# current_sense.net
KiCad netlist of a schematic drawn in Altium Designer
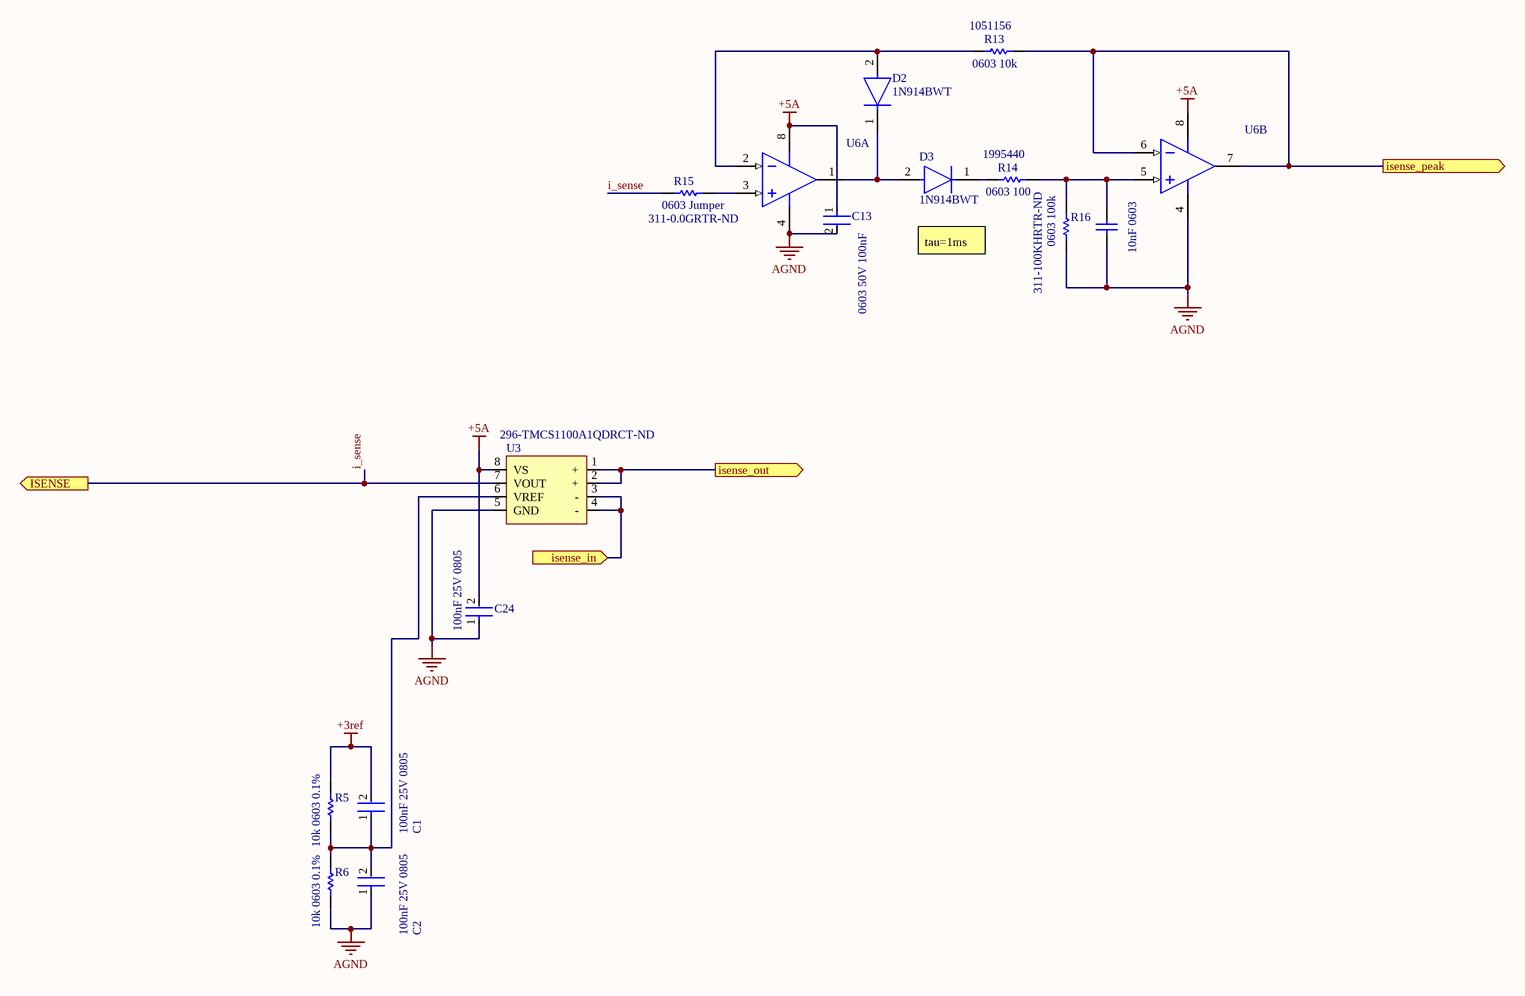
[diagram p0: current_sense.SchDoc]

(export (version "E")
  (design (tool "Eeschema 10.0.6"))
  (components
    (comp (ref "10nF 0603")
      (value "06035C-103KAT2A")
      (footprint "CAPC1608X90X35LL15T15")
      (fields (field (name "MANUFACTURER") "AVX Interconnect / Elco"))
      (libsource (lib "Altium Content Vault") (part "CAP"))
    )
    (comp (ref "C1")
      (value "100nF 25V 0805")
      (footprint "FP-CC0805-0_85-MFG")
      (description "CAP CER 0.1UF 25V X7R 0805")
      (fields (field (name "MANUFACTURER PART NUMBER") "CC0805KRX7R8BB104") (field (name "TOLERANCE") "0.1"))
      (libsource (lib "Altium Content Vault") (part "11868f565c42a9108669ba33697ecf6"))
    )
    (comp (ref "C2")
      (value "100nF 25V 0805")
      (footprint "FP-CC0805-0_85-MFG")
      (description "CAP CER 0.1UF 25V X7R 0805")
      (fields (field (name "MANUFACTURER PART NUMBER") "CC0805KRX7R8BB104") (field (name "TOLERANCE") "0.1"))
      (libsource (lib "Altium Content Vault") (part "11868f565c42a9108669ba33697ecf6"))
    )
    (comp (ref "C13")
      (value "0603 50V 100nF")
      (footprint "FP-CGA3E-0_3-0_1-IPC_A")
      (description "Cap Ceramic 100nF 50V X7R 10% Pad SMD 0603 +125°C Automotive T/R\r\nCGA3E2X7R1H104K080AA")
      (fields (field (name "TOLERANCE") "10%") (field (name "VOLTAGE") "50V"))
      (libsource (lib "Altium Content Vault") (part "b4654b650e69147ec39a6b967a45e02"))
    )
    (comp (ref "C24")
      (value "100nF 25V 0805")
      (footprint "FP-CC0805-0_85-MFG")
      (description "CAP CER 0.1UF 25V X7R 0805")
      (fields (field (name "MANUFACTURER PART NUMBER") "CC0805KRX7R8BB104") (field (name "TOLERANCE") "0.1"))
      (libsource (lib "Altium Content Vault") (part "11868f565c42a9108669ba33697ecf6"))
    )
    (comp (ref "D2")
      (value "1N914BWT")
      (footprint "FP-502-01-MFG")
      (description "DIODE GEN PURP 75V 200MA SOD523F")
      (fields
        (field (name "OCTOPART") "https://octopart.com/1n914bwt-on+semiconductor-84323166")
        (field (name "MANUFACTURER") "ON Semiconductor")
      )
      (libsource (lib "Altium Content Vault") (part "d7152d700b627762746794eb795d46e"))
    )
    (comp (ref "D3")
      (value "1N914BWT")
      (footprint "FP-502-01-MFG")
      (description "DIODE GEN PURP 75V 200MA SOD523F")
      (fields
        (field (name "OCTOPART") "https://octopart.com/1n914bwt-on+semiconductor-84323166")
        (field (name "MANUFACTURER") "ON Semiconductor")
      )
      (libsource (lib "Altium Content Vault") (part "d7152d700b627762746794eb795d46e"))
    )
    (comp (ref "R5")
      (value "10k 0603 0.1%")
      (footprint "RESC1608X55X30ML20T20")
      (description "ERA-3AEB103V")
      (fields (field (name "MANUFACTURER") "Panasonic"))
      (libsource (lib "Altium Content Vault") (part "RES"))
    )
    (comp (ref "R6")
      (value "10k 0603 0.1%")
      (footprint "RESC1608X55X30ML20T20")
      (description "ERA-3AEB103V")
      (fields (field (name "MANUFACTURER") "Panasonic"))
      (libsource (lib "Altium Content Vault") (part "RES"))
    )
    (comp (ref "R13")
      (value "0603 10k")
      (footprint "RES 0603_1608")
      (description "Resistor")
      (fields (field (name "SUPPLIER PART NUMBER 1") "1051156") (field (name "PUBLISHER") "Altium Limited"))
      (libsource (lib "Miscellaneous Devices") (part "Res1"))
    )
    (comp (ref "R14")
      (value "0603 100")
      (footprint "RES 0603_1608")
      (description "Resistor")
      (fields (field (name "SUPPLIER PART NUMBER 1") "1995440") (field (name "PUBLISHER") "Altium Limited"))
      (libsource (lib "Miscellaneous Devices") (part "Res1"))
    )
    (comp (ref "R15")
      (value "0603 Jumper")
      (footprint "RES 0603_1608")
      (description "Resistor")
      (fields
        (field (name "SUPPLIER PART NUMBER 1") "311-0.0GRTR-ND")
        (field (name "PUBLISHER") "Altium Limited")
      )
      (libsource (lib "Miscellaneous Devices") (part "Res1"))
    )
    (comp (ref "R16")
      (value "0603 100k")
      (footprint "RES 0603_1608")
      (description "Resistor")
      (fields
        (field (name "SUPPLIER PART NUMBER 1") "311-100KHRTR-ND")
        (field (name "PUBLISHER") "Altium Limited")
      )
      (libsource (lib "Miscellaneous Devices") (part "Res1"))
    )
    (comp (ref "U3")
      (value "TMCS1100A1QDR")
      (footprint "SOIC8")
      (description "TMCS1100A1QDR\r\n50mV/A , 1.8mOhm , 3V-5.5V")
      (fields (field (name "SUPPLIER PART NUMBER 1") "296-TMCS1100A1QDRCT-ND"))
      (libsource (lib "coil_driver_lib") (part "TMCS1100A1QDR"))
    )
    (comp (ref "U6")
      (value "LTC6244HMS8#TRPBF")
      (footprint "LT-MS8-8_L")
      (fields
        (field (name "LINEAR TECHNOLOGY PART NUMBER") "LTC6244")
        (field (name "MANUFACTURER") "Linear Technology")
      )
      (libsource (lib "Altium Content Vault") (part "LT-LTC6244-MS8-8"))
    )
  )
  (nets
    (net (code "1") (name "+3ref") (class "Default")
      (node (ref "C1") (pin "2") (pinfunction "2_2") (pintype "passive"))
      (node (ref "R5") (pin "2") (pinfunction "2_2") (pintype "passive"))
    )
    (net (code "2") (name "+5A") (class "Default")
      (node (ref "C13") (pin "1") (pinfunction "1_1") (pintype "passive"))
      (node (ref "C24") (pin "2") (pinfunction "2_2") (pintype "passive"))
      (node (ref "U3") (pin "8") (pinfunction "VS_8") (pintype "power_in"))
      (node (ref "U6") (pin "8") (pinfunction "V+_8") (pintype "power_in"))
    )
    (net (code "3") (name "/i_sense") (class "Default")
      (node (ref "R15") (pin "1") (pinfunction "1_1") (pintype "passive"))
      (node (ref "U3") (pin "7") (pinfunction "VOUT_7") (pintype "power_in"))
    )
    (net (code "4") (name "/isense_in") (class "Default")
      (node (ref "U3") (pin "3") (pinfunction "-_3") (pintype "power_in"))
      (node (ref "U3") (pin "4") (pinfunction "-_4") (pintype "power_in"))
    )
    (net (code "5") (name "/isense_out") (class "Default")
      (node (ref "U3") (pin "1") (pinfunction "+_1") (pintype "power_in"))
      (node (ref "U3") (pin "2") (pinfunction "+_2") (pintype "power_in"))
    )
    (net (code "6") (name "/isense_peak") (class "Default")
      (node (ref "R13") (pin "2") (pinfunction "2_2") (pintype "passive"))
      (node (ref "U6") (pin "6") (pinfunction "IN-_B_6") (pintype "input"))
      (node (ref "U6") (pin "7") (pinfunction "OUT_B_7") (pintype "tri_state"))
    )
    (net (code "7") (name "AGND") (class "Default")
      (node (ref "10nF 0603") (pin "1") (pinfunction "1_1") (pintype "passive"))
      (node (ref "C13") (pin "2") (pinfunction "2_2") (pintype "passive"))
      (node (ref "C2") (pin "1") (pinfunction "1_1") (pintype "passive"))
      (node (ref "C24") (pin "1") (pinfunction "1_1") (pintype "passive"))
      (node (ref "R16") (pin "1") (pinfunction "1_1") (pintype "passive"))
      (node (ref "R6") (pin "1") (pinfunction "1_1") (pintype "passive"))
      (node (ref "U3") (pin "5") (pinfunction "GND_5") (pintype "power_in"))
      (node (ref "U6") (pin "4") (pinfunction "V-_4") (pintype "power_in"))
    )
    (net (code "8") (name "Net-(D2-A)") (class "Default")
      (node (ref "D2") (pin "2") (pinfunction "A_2") (pintype "passive"))
      (node (ref "R13") (pin "1") (pinfunction "1_1") (pintype "passive"))
      (node (ref "U6") (pin "2") (pinfunction "IN-_A_2") (pintype "input"))
    )
    (net (code "9") (name "Net-(D2-C)") (class "Default")
      (node (ref "D2") (pin "1") (pinfunction "C_1") (pintype "passive"))
      (node (ref "D3") (pin "2") (pinfunction "A_2") (pintype "passive"))
      (node (ref "U6") (pin "1") (pinfunction "OUT_A_1") (pintype "tri_state"))
    )
    (net (code "10") (name "Net-(D3-C)") (class "Default")
      (node (ref "D3") (pin "1") (pinfunction "C_1") (pintype "passive"))
      (node (ref "R14") (pin "1") (pinfunction "1_1") (pintype "passive"))
    )
    (net (code "11") (name "Net-(U3-VREF)") (class "Default")
      (node (ref "C1") (pin "1") (pinfunction "1_1") (pintype "passive"))
      (node (ref "C2") (pin "2") (pinfunction "2_2") (pintype "passive"))
      (node (ref "R5") (pin "1") (pinfunction "1_1") (pintype "passive"))
      (node (ref "R6") (pin "2") (pinfunction "2_2") (pintype "passive"))
      (node (ref "U3") (pin "6") (pinfunction "VREF_6") (pintype "power_in"))
    )
    (net (code "12") (name "Net-(U6A-IN+_A)") (class "Default")
      (node (ref "R15") (pin "2") (pinfunction "2_2") (pintype "passive"))
      (node (ref "U6") (pin "3") (pinfunction "IN+_A_3") (pintype "input"))
    )
    (net (code "13") (name "Net-(U6B-IN+_B)") (class "Default")
      (node (ref "10nF 0603") (pin "2") (pinfunction "2_2") (pintype "passive"))
      (node (ref "R14") (pin "2") (pinfunction "2_2") (pintype "passive"))
      (node (ref "R16") (pin "2") (pinfunction "2_2") (pintype "passive"))
      (node (ref "U6") (pin "5") (pinfunction "IN+_B_5") (pintype "input"))
    )
  )
)
